# OpenMoteSTM-Border_MCU.net
KiCad netlist of a schematic drawn in Altium Designer
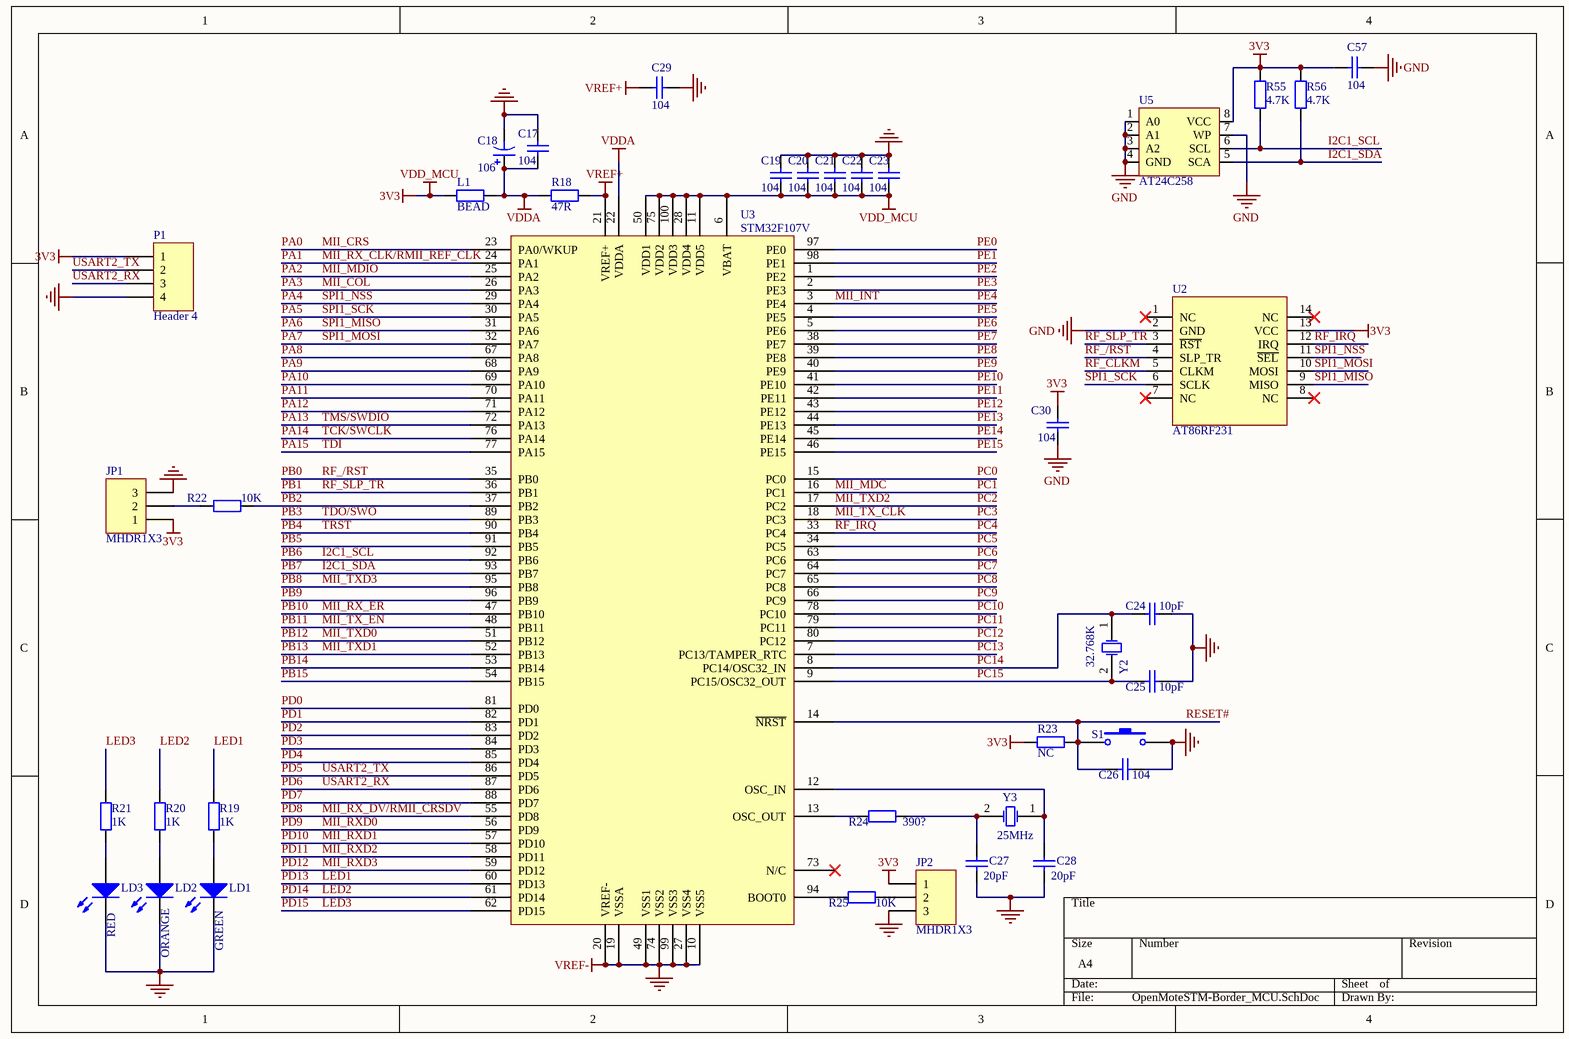
[diagram p0: OpenMoteSTM-Border_MCU.SchDoc]

(export (version "E")
  (design (tool "Eeschema 10.0.6"))
  (components
    (comp (ref "C17")
      (value "104")
      (footprint "0603")
      (description "Capacitor")
      (fields (field (name "Comment") "Cap") (field (name "PUBLISHER") "Altium Limited"))
      (libsource (lib "Miscellaneous Devices") (part "Cap"))
    )
    (comp (ref "C18")
      (value "106")
      (footprint "1210")
      (description "Polarized Capacitor (Radial)")
      (fields (field (name "Comment") "Cap Pol1") (field (name "PUBLISHER") "Altium Limited"))
      (libsource (lib "Miscellaneous Devices") (part "Cap Pol1"))
    )
    (comp (ref "C19")
      (value "104")
      (footprint "0603")
      (description "Capacitor")
      (fields (field (name "Comment") "Cap") (field (name "PUBLISHER") "Altium Limited"))
      (libsource (lib "Miscellaneous Devices") (part "Cap"))
    )
    (comp (ref "C20")
      (value "104")
      (footprint "0603")
      (description "Capacitor")
      (fields (field (name "Comment") "Cap") (field (name "PUBLISHER") "Altium Limited"))
      (libsource (lib "Miscellaneous Devices") (part "Cap"))
    )
    (comp (ref "C21")
      (value "104")
      (footprint "0603")
      (description "Capacitor")
      (fields (field (name "Comment") "Cap") (field (name "PUBLISHER") "Altium Limited"))
      (libsource (lib "Miscellaneous Devices") (part "Cap"))
    )
    (comp (ref "C22")
      (value "104")
      (footprint "0603")
      (description "Capacitor")
      (fields (field (name "Comment") "Cap") (field (name "PUBLISHER") "Altium Limited"))
      (libsource (lib "Miscellaneous Devices") (part "Cap"))
    )
    (comp (ref "C23")
      (value "104")
      (footprint "0603")
      (description "Capacitor")
      (fields (field (name "Comment") "Cap") (field (name "PUBLISHER") "Altium Limited"))
      (libsource (lib "Miscellaneous Devices") (part "Cap"))
    )
    (comp (ref "C24")
      (value "10pF")
      (footprint "0603")
      (description "Capacitor")
      (fields (field (name "Comment") "Cap") (field (name "PUBLISHER") "Altium Limited"))
      (libsource (lib "Miscellaneous Devices") (part "Cap"))
    )
    (comp (ref "C25")
      (value "10pF")
      (footprint "0603")
      (description "Capacitor")
      (fields (field (name "Comment") "Cap") (field (name "PUBLISHER") "Altium Limited"))
      (libsource (lib "Miscellaneous Devices") (part "Cap"))
    )
    (comp (ref "C26")
      (value "104")
      (footprint "0603")
      (description "Capacitor")
      (fields (field (name "Comment") "Cap") (field (name "PUBLISHER") "Altium Limited"))
      (libsource (lib "Miscellaneous Devices") (part "Cap"))
    )
    (comp (ref "C27")
      (value "20pF")
      (footprint "0603")
      (description "Capacitor")
      (fields (field (name "Comment") "Cap") (field (name "PUBLISHER") "Altium Limited"))
      (libsource (lib "Miscellaneous Devices") (part "Cap"))
    )
    (comp (ref "C28")
      (value "20pF")
      (footprint "0603")
      (description "Capacitor")
      (fields (field (name "Comment") "Cap") (field (name "PUBLISHER") "Altium Limited"))
      (libsource (lib "Miscellaneous Devices") (part "Cap"))
    )
    (comp (ref "C29")
      (value "104")
      (footprint "0603")
      (description "Capacitor")
      (fields (field (name "Comment") "Cap") (field (name "PUBLISHER") "Altium Limited"))
      (libsource (lib "Miscellaneous Devices") (part "Cap"))
    )
    (comp (ref "C30")
      (value "104")
      (footprint "0603")
      (description "Capacitor")
      (fields (field (name "Comment") "Cap") (field (name "PUBLISHER") "Altium Limited"))
      (libsource (lib "Miscellaneous Devices") (part "Cap"))
    )
    (comp (ref "C57")
      (value "104")
      (footprint "0603")
      (description "Capacitor")
      (fields (field (name "Comment") "Cap") (field (name "PUBLISHER") "Altium Limited"))
      (libsource (lib "Miscellaneous Devices") (part "Cap"))
    )
    (comp (ref "JP1")
      (value "MHDR1X3")
      (footprint "MHDR1X3")
      (description "Header, 3-Pin")
      (fields (field (name "PUBLISHER") "Altium Limited"))
      (libsource (lib "Miscellaneous Connectors") (part "MHDR1X3"))
    )
    (comp (ref "JP2")
      (value "MHDR1X3")
      (footprint "MHDR1X3")
      (description "Header, 3-Pin")
      (fields (field (name "PUBLISHER") "Altium Limited"))
      (libsource (lib "") (part "MHDR1X3_1"))
    )
    (comp (ref "L1")
      (value "BEAD")
      (footprint "0603")
      (description "Resistor")
      (fields (field (name "Comment") "Res2") (field (name "PUBLISHER") "Altium Limited"))
      (libsource (lib "Miscellaneous Devices") (part "Res2"))
    )
    (comp (ref "LD1")
      (value "GREEN")
      (footprint "0603")
      (description "Typical RED, GREEN, YELLOW, AMBER GaAs LED")
      (fields (field (name "PUBLISHER") "Altium Limited"))
      (libsource (lib "Miscellaneous Devices") (part "LED2"))
    )
    (comp (ref "LD2")
      (value "ORANGE")
      (footprint "0603")
      (description "Typical RED, GREEN, YELLOW, AMBER GaAs LED")
      (fields (field (name "PUBLISHER") "Altium Limited"))
      (libsource (lib "Miscellaneous Devices") (part "LED2"))
    )
    (comp (ref "LD3")
      (value "RED")
      (footprint "0603")
      (description "Typical RED, GREEN, YELLOW, AMBER GaAs LED")
      (fields (field (name "PUBLISHER") "Altium Limited"))
      (libsource (lib "Miscellaneous Devices") (part "LED2"))
    )
    (comp (ref "P1")
      (value "Header 4")
      (footprint "HDR1X4")
      (description "Header, 4-Pin")
      (fields (field (name "PUBLISHER") "Altium Limited"))
      (libsource (lib "Miscellaneous Connectors") (part "Header 4"))
    )
    (comp (ref "R18")
      (value "47R")
      (footprint "0603")
      (description "Resistor")
      (fields (field (name "Comment") "Res2") (field (name "PUBLISHER") "Altium Limited"))
      (libsource (lib "Miscellaneous Devices") (part "Res2"))
    )
    (comp (ref "R19")
      (value "1K")
      (footprint "0603")
      (description "Resistor")
      (fields (field (name "Comment") "Res2") (field (name "PUBLISHER") "Altium Limited"))
      (libsource (lib "") (part "Res2_2"))
    )
    (comp (ref "R20")
      (value "1K")
      (footprint "0603")
      (description "Resistor")
      (fields (field (name "Comment") "Res2") (field (name "PUBLISHER") "Altium Limited"))
      (libsource (lib "") (part "Res2_2"))
    )
    (comp (ref "R21")
      (value "1K")
      (footprint "0603")
      (description "Resistor")
      (fields (field (name "Comment") "Res2") (field (name "PUBLISHER") "Altium Limited"))
      (libsource (lib "") (part "Res2_2"))
    )
    (comp (ref "R22")
      (value "10K")
      (footprint "0603")
      (description "Resistor")
      (fields (field (name "Comment") "Res2") (field (name "PUBLISHER") "Altium Limited"))
      (libsource (lib "") (part "Res2_1"))
    )
    (comp (ref "R23")
      (value "NC")
      (footprint "0603")
      (description "Resistor")
      (fields (field (name "Comment") "Res2") (field (name "PUBLISHER") "Altium Limited"))
      (libsource (lib "") (part "Res2_1"))
    )
    (comp (ref "R24")
      (value "390?")
      (footprint "0603")
      (description "Resistor")
      (fields (field (name "Comment") "Res2") (field (name "PUBLISHER") "Altium Limited"))
      (libsource (lib "Miscellaneous Devices") (part "Res2"))
    )
    (comp (ref "R25")
      (value "10K")
      (footprint "0603")
      (description "Resistor")
      (fields (field (name "Comment") "Res2") (field (name "PUBLISHER") "Altium Limited"))
      (libsource (lib "") (part "Res2_1"))
    )
    (comp (ref "R55")
      (value "4.7K")
      (footprint "0603")
      (description "Resistor")
      (fields (field (name "Comment") "Res2") (field (name "PUBLISHER") "Altium Limited"))
      (libsource (lib "") (part "Res2_2"))
    )
    (comp (ref "R56")
      (value "4.7K")
      (footprint "0603")
      (description "Resistor")
      (fields (field (name "Comment") "Res2") (field (name "PUBLISHER") "Altium Limited"))
      (libsource (lib "") (part "Res2_2"))
    )
    (comp (ref "S1")
      (value "SW-PB")
      (footprint "KEY-SMD")
      (description "Switch")
      (fields (field (name "PUBLISHER") "Altium Limited"))
      (libsource (lib "Miscellaneous Devices") (part "SW-PB"))
    )
    (comp (ref "U2")
      (value "AT86RF231")
      (footprint "AT86RF231")
      (libsource (lib "OpenMoteSTM-Border") (part "AT86RF231"))
    )
    (comp (ref "U3")
      (value "STM32F107V")
      (footprint "STM32F107")
      (libsource (lib "OpenMoteSTM-Border") (part "STM32F107V"))
    )
    (comp (ref "U5")
      (value "AT24C258")
      (footprint "AT24C256C")
      (libsource (lib "OpenMoteSTM-Border") (part "AT24C258"))
    )
    (comp (ref "Y2")
      (value "32.768K")
      (footprint "32.768K")
      (description "Crystal Oscillator")
      (fields (field (name "PUBLISHER") "Altium Limited"))
      (libsource (lib "Miscellaneous Devices") (part "XTAL"))
    )
    (comp (ref "Y3")
      (value "25MHz")
      (footprint "XTAL")
      (description "Crystal Oscillator")
      (fields (field (name "PUBLISHER") "Altium Limited"))
      (libsource (lib "Miscellaneous Devices") (part "XTAL"))
    )
  )
  (nets
    (net (code "1") (name "/I2C1_SCL") (class "Default")
      (node (ref "R55") (pin "2") (pinfunction "2_2") (pintype "passive"))
      (node (ref "U3") (pin "92") (pinfunction "PB6_92") (pintype "passive"))
      (node (ref "U5") (pin "6") (pinfunction "SCL_6") (pintype "passive"))
    )
    (net (code "2") (name "/I2C1_SDA") (class "Default")
      (node (ref "R56") (pin "2") (pinfunction "2_2") (pintype "passive"))
      (node (ref "U3") (pin "93") (pinfunction "PB7_93") (pintype "passive"))
      (node (ref "U5") (pin "5") (pinfunction "SCA_5") (pintype "passive"))
    )
    (net (code "3") (name "/LED1") (class "Default")
      (node (ref "R19") (pin "1") (pinfunction "1_1") (pintype "passive"))
      (node (ref "U3") (pin "60") (pinfunction "PD13_60") (pintype "passive"))
    )
    (net (code "4") (name "/LED2") (class "Default")
      (node (ref "R20") (pin "1") (pinfunction "1_1") (pintype "passive"))
      (node (ref "U3") (pin "61") (pinfunction "PD14_61") (pintype "passive"))
    )
    (net (code "5") (name "/LED3") (class "Default")
      (node (ref "R21") (pin "1") (pinfunction "1_1") (pintype "passive"))
      (node (ref "U3") (pin "62") (pinfunction "PD15_62") (pintype "passive"))
    )
    (net (code "6") (name "/MII_COL") (class "Default")
      (node (ref "U3") (pin "26") (pinfunction "PA3_26") (pintype "passive"))
    )
    (net (code "7") (name "/MII_CRS") (class "Default")
      (node (ref "U3") (pin "23") (pinfunction "PA0/WKUP_23") (pintype "passive"))
    )
    (net (code "8") (name "/MII_INT") (class "Default")
      (node (ref "U3") (pin "3") (pinfunction "PE4_3") (pintype "passive"))
    )
    (net (code "9") (name "/MII_MDC") (class "Default")
      (node (ref "U3") (pin "16") (pinfunction "PC1_16") (pintype "passive"))
    )
    (net (code "10") (name "/MII_MDIO") (class "Default")
      (node (ref "U3") (pin "25") (pinfunction "PA2_25") (pintype "passive"))
    )
    (net (code "11") (name "/MII_RXD0") (class "Default")
      (node (ref "U3") (pin "56") (pinfunction "PD9_56") (pintype "passive"))
    )
    (net (code "12") (name "/MII_RXD1") (class "Default")
      (node (ref "U3") (pin "57") (pinfunction "PD10_57") (pintype "passive"))
    )
    (net (code "13") (name "/MII_RXD2") (class "Default")
      (node (ref "U3") (pin "58") (pinfunction "PD11_58") (pintype "passive"))
    )
    (net (code "14") (name "/MII_RXD3") (class "Default")
      (node (ref "U3") (pin "59") (pinfunction "PD12_59") (pintype "passive"))
    )
    (net (code "15") (name "/MII_RX_CLK{slash}RMII_REF_CLK") (class "Default")
      (node (ref "U3") (pin "24") (pinfunction "PA1_24") (pintype "passive"))
    )
    (net (code "16") (name "/MII_RX_DV{slash}RMII_CRSDV") (class "Default")
      (node (ref "U3") (pin "55") (pinfunction "PD8_55") (pintype "passive"))
    )
    (net (code "17") (name "/MII_RX_ER") (class "Default")
      (node (ref "U3") (pin "47") (pinfunction "PB10_47") (pintype "passive"))
    )
    (net (code "18") (name "/MII_TXD0") (class "Default")
      (node (ref "U3") (pin "51") (pinfunction "PB12_51") (pintype "passive"))
    )
    (net (code "19") (name "/MII_TXD1") (class "Default")
      (node (ref "U3") (pin "52") (pinfunction "PB13_52") (pintype "passive"))
    )
    (net (code "20") (name "/MII_TXD2") (class "Default")
      (node (ref "U3") (pin "17") (pinfunction "PC2_17") (pintype "passive"))
    )
    (net (code "21") (name "/MII_TXD3") (class "Default")
      (node (ref "U3") (pin "95") (pinfunction "PB8_95") (pintype "passive"))
    )
    (net (code "22") (name "/MII_TX_CLK") (class "Default")
      (node (ref "U3") (pin "18") (pinfunction "PC3_18") (pintype "passive"))
    )
    (net (code "23") (name "/MII_TX_EN") (class "Default")
      (node (ref "U3") (pin "48") (pinfunction "PB11_48") (pintype "passive"))
    )
    (net (code "24") (name "/PA4") (class "Default")
      (node (ref "U2") (pin "11") (pinfunction "~{SEL}_11") (pintype "passive"))
      (node (ref "U3") (pin "29") (pinfunction "PA4_29") (pintype "passive"))
    )
    (net (code "25") (name "/PA5") (class "Default")
      (node (ref "U2") (pin "6") (pinfunction "SCLK_6") (pintype "passive"))
      (node (ref "U3") (pin "30") (pinfunction "PA5_30") (pintype "passive"))
    )
    (net (code "26") (name "/PA6") (class "Default")
      (node (ref "U2") (pin "9") (pinfunction "MISO_9") (pintype "passive"))
      (node (ref "U3") (pin "31") (pinfunction "PA6_31") (pintype "passive"))
    )
    (net (code "27") (name "/PA7") (class "Default")
      (node (ref "U2") (pin "10") (pinfunction "MOSI_10") (pintype "passive"))
      (node (ref "U3") (pin "32") (pinfunction "PA7_32") (pintype "passive"))
    )
    (net (code "28") (name "/PA8") (class "Default")
      (node (ref "U3") (pin "67") (pinfunction "PA8_67") (pintype "passive"))
    )
    (net (code "29") (name "/PA9") (class "Default")
      (node (ref "U3") (pin "68") (pinfunction "PA9_68") (pintype "passive"))
    )
    (net (code "30") (name "/PA10") (class "Default")
      (node (ref "U3") (pin "69") (pinfunction "PA10_69") (pintype "passive"))
    )
    (net (code "31") (name "/PA11") (class "Default")
      (node (ref "U3") (pin "70") (pinfunction "PA11_70") (pintype "passive"))
    )
    (net (code "32") (name "/PA12") (class "Default")
      (node (ref "U3") (pin "71") (pinfunction "PA12_71") (pintype "passive"))
    )
    (net (code "33") (name "/PA13") (class "Default")
      (node (ref "U3") (pin "72") (pinfunction "PA13_72") (pintype "passive"))
    )
    (net (code "34") (name "/PA14") (class "Default")
      (node (ref "U3") (pin "76") (pinfunction "PA14_76") (pintype "passive"))
    )
    (net (code "35") (name "/PA15") (class "Default")
      (node (ref "U3") (pin "77") (pinfunction "PA15_77") (pintype "passive"))
    )
    (net (code "36") (name "/PB0") (class "Default")
      (node (ref "U2") (pin "4") (pinfunction "SLP_TR_4") (pintype "passive"))
      (node (ref "U3") (pin "35") (pinfunction "PB0_35") (pintype "passive"))
    )
    (net (code "37") (name "/PB1") (class "Default")
      (node (ref "U2") (pin "3") (pinfunction "~{RST}_3") (pintype "passive"))
      (node (ref "U3") (pin "36") (pinfunction "PB1_36") (pintype "passive"))
    )
    (net (code "38") (name "/PB2") (class "Default")
      (node (ref "R22") (pin "1") (pinfunction "1_1") (pintype "passive"))
      (node (ref "U3") (pin "37") (pinfunction "PB2_37") (pintype "passive"))
    )
    (net (code "39") (name "/PB3") (class "Default")
      (node (ref "U3") (pin "89") (pinfunction "PB3_89") (pintype "passive"))
    )
    (net (code "40") (name "/PB4") (class "Default")
      (node (ref "U3") (pin "90") (pinfunction "PB4_90") (pintype "passive"))
    )
    (net (code "41") (name "/PB5") (class "Default")
      (node (ref "U3") (pin "91") (pinfunction "PB5_91") (pintype "passive"))
    )
    (net (code "42") (name "/PB9") (class "Default")
      (node (ref "U3") (pin "96") (pinfunction "PB9_96") (pintype "passive"))
    )
    (net (code "43") (name "/PB14") (class "Default")
      (node (ref "U3") (pin "53") (pinfunction "PB14_53") (pintype "passive"))
    )
    (net (code "44") (name "/PB15") (class "Default")
      (node (ref "U3") (pin "54") (pinfunction "PB15_54") (pintype "passive"))
    )
    (net (code "45") (name "/PC0") (class "Default")
      (node (ref "U3") (pin "15") (pinfunction "PC0_15") (pintype "passive"))
    )
    (net (code "46") (name "/PC4") (class "Default")
      (node (ref "U2") (pin "12") (pinfunction "IRQ_12") (pintype "passive"))
      (node (ref "U3") (pin "33") (pinfunction "PC4_33") (pintype "passive"))
    )
    (net (code "47") (name "/PC5") (class "Default")
      (node (ref "U3") (pin "34") (pinfunction "PC5_34") (pintype "passive"))
    )
    (net (code "48") (name "/PC6") (class "Default")
      (node (ref "U3") (pin "63") (pinfunction "PC6_63") (pintype "passive"))
    )
    (net (code "49") (name "/PC7") (class "Default")
      (node (ref "U3") (pin "64") (pinfunction "PC7_64") (pintype "passive"))
    )
    (net (code "50") (name "/PC8") (class "Default")
      (node (ref "U3") (pin "65") (pinfunction "PC8_65") (pintype "passive"))
    )
    (net (code "51") (name "/PC9") (class "Default")
      (node (ref "U3") (pin "66") (pinfunction "PC9_66") (pintype "passive"))
    )
    (net (code "52") (name "/PC10") (class "Default")
      (node (ref "U3") (pin "78") (pinfunction "PC10_78") (pintype "passive"))
    )
    (net (code "53") (name "/PC11") (class "Default")
      (node (ref "U3") (pin "79") (pinfunction "PC11_79") (pintype "passive"))
    )
    (net (code "54") (name "/PC12") (class "Default")
      (node (ref "U3") (pin "80") (pinfunction "PC12_80") (pintype "passive"))
    )
    (net (code "55") (name "/PC13") (class "Default")
      (node (ref "U3") (pin "7") (pinfunction "PC13/TAMPER_RTC_7") (pintype "passive"))
    )
    (net (code "56") (name "/PC14") (class "Default")
      (node (ref "C24") (pin "2") (pinfunction "2_2") (pintype "passive"))
      (node (ref "U3") (pin "8") (pinfunction "PC14/OSC32_IN_8") (pintype "passive"))
      (node (ref "Y2") (pin "1") (pinfunction "OSC1_1") (pintype "passive"))
    )
    (net (code "57") (name "/PC15") (class "Default")
      (node (ref "C25") (pin "1") (pinfunction "1_1") (pintype "passive"))
      (node (ref "U3") (pin "9") (pinfunction "PC15/OSC32_OUT_9") (pintype "passive"))
      (node (ref "Y2") (pin "2") (pinfunction "OSC2_2") (pintype "passive"))
    )
    (net (code "58") (name "/PD0") (class "Default")
      (node (ref "U3") (pin "81") (pinfunction "PD0_81") (pintype "passive"))
    )
    (net (code "59") (name "/PD1") (class "Default")
      (node (ref "U3") (pin "82") (pinfunction "PD1_82") (pintype "passive"))
    )
    (net (code "60") (name "/PD2") (class "Default")
      (node (ref "U3") (pin "83") (pinfunction "PD2_83") (pintype "passive"))
    )
    (net (code "61") (name "/PD3") (class "Default")
      (node (ref "U3") (pin "84") (pinfunction "PD3_84") (pintype "passive"))
    )
    (net (code "62") (name "/PD4") (class "Default")
      (node (ref "U3") (pin "85") (pinfunction "PD4_85") (pintype "passive"))
    )
    (net (code "63") (name "/PD5") (class "Default")
      (node (ref "P1") (pin "2") (pinfunction "2_2") (pintype "passive"))
      (node (ref "U3") (pin "86") (pinfunction "PD5_86") (pintype "passive"))
    )
    (net (code "64") (name "/PD6") (class "Default")
      (node (ref "P1") (pin "3") (pinfunction "3_3") (pintype "passive"))
      (node (ref "U3") (pin "87") (pinfunction "PD6_87") (pintype "passive"))
    )
    (net (code "65") (name "/PD7") (class "Default")
      (node (ref "U3") (pin "88") (pinfunction "PD7_88") (pintype "passive"))
    )
    (net (code "66") (name "/PE0") (class "Default")
      (node (ref "U3") (pin "97") (pinfunction "PE0_97") (pintype "passive"))
    )
    (net (code "67") (name "/PE1") (class "Default")
      (node (ref "U3") (pin "98") (pinfunction "PE1_98") (pintype "passive"))
    )
    (net (code "68") (name "/PE2") (class "Default")
      (node (ref "U3") (pin "1") (pinfunction "PE2_1") (pintype "passive"))
    )
    (net (code "69") (name "/PE3") (class "Default")
      (node (ref "U3") (pin "2") (pinfunction "PE3_2") (pintype "passive"))
    )
    (net (code "70") (name "/PE5") (class "Default")
      (node (ref "U3") (pin "4") (pinfunction "PE5_4") (pintype "passive"))
    )
    (net (code "71") (name "/PE6") (class "Default")
      (node (ref "U3") (pin "5") (pinfunction "PE6_5") (pintype "passive"))
    )
    (net (code "72") (name "/PE7") (class "Default")
      (node (ref "U3") (pin "38") (pinfunction "PE7_38") (pintype "passive"))
    )
    (net (code "73") (name "/PE8") (class "Default")
      (node (ref "U3") (pin "39") (pinfunction "PE8_39") (pintype "passive"))
    )
    (net (code "74") (name "/PE9") (class "Default")
      (node (ref "U3") (pin "40") (pinfunction "PE9_40") (pintype "passive"))
    )
    (net (code "75") (name "/PE10") (class "Default")
      (node (ref "U3") (pin "41") (pinfunction "PE10_41") (pintype "passive"))
    )
    (net (code "76") (name "/PE11") (class "Default")
      (node (ref "U3") (pin "42") (pinfunction "PE11_42") (pintype "passive"))
    )
    (net (code "77") (name "/PE12") (class "Default")
      (node (ref "U3") (pin "43") (pinfunction "PE12_43") (pintype "passive"))
    )
    (net (code "78") (name "/PE13") (class "Default")
      (node (ref "U3") (pin "44") (pinfunction "PE13_44") (pintype "passive"))
    )
    (net (code "79") (name "/PE14") (class "Default")
      (node (ref "U3") (pin "45") (pinfunction "PE14_45") (pintype "passive"))
    )
    (net (code "80") (name "/PE15") (class "Default")
      (node (ref "U3") (pin "46") (pinfunction "PE15_46") (pintype "passive"))
    )
    (net (code "81") (name "/RESET#") (class "Default")
      (node (ref "C26") (pin "2") (pinfunction "2_2") (pintype "passive"))
      (node (ref "R23") (pin "1") (pinfunction "1_1") (pintype "passive"))
      (node (ref "S1") (pin "1") (pinfunction "1_1") (pintype "passive"))
      (node (ref "U3") (pin "14") (pinfunction "~{NRST}_14") (pintype "passive"))
    )
    (net (code "82") (name "/RF_CLKM") (class "Default")
      (node (ref "U2") (pin "5") (pinfunction "CLKM_5") (pintype "passive"))
    )
    (net (code "83") (name "3V3") (class "Default")
      (node (ref "C19") (pin "1") (pinfunction "1_1") (pintype "passive"))
      (node (ref "C20") (pin "1") (pinfunction "1_1") (pintype "passive"))
      (node (ref "C21") (pin "1") (pinfunction "1_1") (pintype "passive"))
      (node (ref "C22") (pin "1") (pinfunction "1_1") (pintype "passive"))
      (node (ref "C23") (pin "1") (pinfunction "1_1") (pintype "passive"))
      (node (ref "C30") (pin "2") (pinfunction "2_2") (pintype "passive"))
      (node (ref "C57") (pin "2") (pinfunction "2_2") (pintype "passive"))
      (node (ref "JP1") (pin "1") (pinfunction "1_1") (pintype "passive"))
      (node (ref "JP2") (pin "1") (pinfunction "1_1") (pintype "passive"))
      (node (ref "L1") (pin "1") (pinfunction "1_1") (pintype "passive"))
      (node (ref "P1") (pin "1") (pinfunction "1_1") (pintype "passive"))
      (node (ref "R23") (pin "2") (pinfunction "2_2") (pintype "passive"))
      (node (ref "R55") (pin "1") (pinfunction "1_1") (pintype "passive"))
      (node (ref "R56") (pin "1") (pinfunction "1_1") (pintype "passive"))
      (node (ref "U2") (pin "13") (pinfunction "VCC_13") (pintype "passive"))
      (node (ref "U3") (pin "100") (pinfunction "VDD3_100") (pintype "passive"))
      (node (ref "U3") (pin "11") (pinfunction "VDD5_11") (pintype "passive"))
      (node (ref "U3") (pin "28") (pinfunction "VDD4_28") (pintype "passive"))
      (node (ref "U3") (pin "50") (pinfunction "VDD1_50") (pintype "passive"))
      (node (ref "U3") (pin "6") (pinfunction "VBAT_6") (pintype "passive"))
      (node (ref "U3") (pin "75") (pinfunction "VDD2_75") (pintype "passive"))
      (node (ref "U5") (pin "8") (pinfunction "VCC_8") (pintype "passive"))
    )
    (net (code "84") (name "GND") (class "Default")
      (node (ref "C17") (pin "2") (pinfunction "2_2") (pintype "passive"))
      (node (ref "C18") (pin "2") (pinfunction "2_2") (pintype "passive"))
      (node (ref "C19") (pin "2") (pinfunction "2_2") (pintype "passive"))
      (node (ref "C20") (pin "2") (pinfunction "2_2") (pintype "passive"))
      (node (ref "C21") (pin "2") (pinfunction "2_2") (pintype "passive"))
      (node (ref "C22") (pin "2") (pinfunction "2_2") (pintype "passive"))
      (node (ref "C23") (pin "2") (pinfunction "2_2") (pintype "passive"))
      (node (ref "C24") (pin "1") (pinfunction "1_1") (pintype "passive"))
      (node (ref "C25") (pin "2") (pinfunction "2_2") (pintype "passive"))
      (node (ref "C26") (pin "1") (pinfunction "1_1") (pintype "passive"))
      (node (ref "C27") (pin "2") (pinfunction "2_2") (pintype "passive"))
      (node (ref "C28") (pin "2") (pinfunction "2_2") (pintype "passive"))
      (node (ref "C29") (pin "2") (pinfunction "2_2") (pintype "passive"))
      (node (ref "C30") (pin "1") (pinfunction "1_1") (pintype "passive"))
      (node (ref "C57") (pin "1") (pinfunction "1_1") (pintype "passive"))
      (node (ref "JP1") (pin "3") (pinfunction "3_3") (pintype "passive"))
      (node (ref "JP2") (pin "3") (pinfunction "3_3") (pintype "passive"))
      (node (ref "LD1") (pin "2") (pinfunction "K_2") (pintype "passive"))
      (node (ref "LD2") (pin "2") (pinfunction "K_2") (pintype "passive"))
      (node (ref "LD3") (pin "2") (pinfunction "K_2") (pintype "passive"))
      (node (ref "P1") (pin "4") (pinfunction "4_4") (pintype "passive"))
      (node (ref "S1") (pin "2") (pinfunction "2_2") (pintype "passive"))
      (node (ref "U2") (pin "2") (pinfunction "GND_2") (pintype "passive"))
      (node (ref "U3") (pin "10") (pinfunction "VSS5_10") (pintype "passive"))
      (node (ref "U3") (pin "19") (pinfunction "VSSA_19") (pintype "passive"))
      (node (ref "U3") (pin "20") (pinfunction "VREF-_20") (pintype "passive"))
      (node (ref "U3") (pin "27") (pinfunction "VSS4_27") (pintype "passive"))
      (node (ref "U3") (pin "49") (pinfunction "VSS1_49") (pintype "passive"))
      (node (ref "U3") (pin "74") (pinfunction "VSS2_74") (pintype "passive"))
      (node (ref "U3") (pin "99") (pinfunction "VSS3_99") (pintype "passive"))
      (node (ref "U5") (pin "1") (pinfunction "A0_1") (pintype "passive"))
      (node (ref "U5") (pin "2") (pinfunction "A1_2") (pintype "passive"))
      (node (ref "U5") (pin "3") (pinfunction "A2_3") (pintype "passive"))
      (node (ref "U5") (pin "4") (pinfunction "GND_4") (pintype "passive"))
      (node (ref "U5") (pin "7") (pinfunction "WP_7") (pintype "passive"))
    )
    (net (code "85") (name "Net-(JP1-Pad2)") (class "Default")
      (node (ref "JP1") (pin "2") (pinfunction "2_2") (pintype "passive"))
      (node (ref "R22") (pin "2") (pinfunction "2_2") (pintype "passive"))
    )
    (net (code "86") (name "Net-(JP2-Pad2)") (class "Default")
      (node (ref "JP2") (pin "2") (pinfunction "2_2") (pintype "passive"))
      (node (ref "R25") (pin "1") (pinfunction "1_1") (pintype "passive"))
    )
    (net (code "87") (name "Net-(LD1-A)") (class "Default")
      (node (ref "LD1") (pin "1") (pinfunction "A_1") (pintype "passive"))
      (node (ref "R19") (pin "2") (pinfunction "2_2") (pintype "passive"))
    )
    (net (code "88") (name "Net-(LD2-A)") (class "Default")
      (node (ref "LD2") (pin "1") (pinfunction "A_1") (pintype "passive"))
      (node (ref "R20") (pin "2") (pinfunction "2_2") (pintype "passive"))
    )
    (net (code "89") (name "Net-(LD3-A)") (class "Default")
      (node (ref "LD3") (pin "1") (pinfunction "A_1") (pintype "passive"))
      (node (ref "R21") (pin "2") (pinfunction "2_2") (pintype "passive"))
    )
    (net (code "90") (name "Net-(U3-BOOT0)") (class "Default")
      (node (ref "R25") (pin "2") (pinfunction "2_2") (pintype "passive"))
      (node (ref "U3") (pin "94") (pinfunction "BOOT0_94") (pintype "passive"))
    )
    (net (code "91") (name "Net-(U3-OSC_IN)") (class "Default")
      (node (ref "C28") (pin "1") (pinfunction "1_1") (pintype "passive"))
      (node (ref "U3") (pin "12") (pinfunction "OSC_IN_12") (pintype "passive"))
      (node (ref "Y3") (pin "1") (pinfunction "OSC1_1") (pintype "passive"))
    )
    (net (code "92") (name "Net-(U3-OSC_OUT)") (class "Default")
      (node (ref "R24") (pin "1") (pinfunction "1_1") (pintype "passive"))
      (node (ref "U3") (pin "13") (pinfunction "OSC_OUT_13") (pintype "passive"))
    )
    (net (code "93") (name "Net-(Y3-OSC2)") (class "Default")
      (node (ref "C27") (pin "1") (pinfunction "1_1") (pintype "passive"))
      (node (ref "R24") (pin "2") (pinfunction "2_2") (pintype "passive"))
      (node (ref "Y3") (pin "2") (pinfunction "OSC2_2") (pintype "passive"))
    )
    (net (code "94") (name "VDDA") (class "Default")
      (node (ref "C17") (pin "1") (pinfunction "1_1") (pintype "passive"))
      (node (ref "C18") (pin "1") (pinfunction "1_1") (pintype "passive"))
      (node (ref "L1") (pin "2") (pinfunction "2_2") (pintype "passive"))
      (node (ref "R18") (pin "1") (pinfunction "1_1") (pintype "passive"))
      (node (ref "U3") (pin "22") (pinfunction "VDDA_22") (pintype "passive"))
    )
    (net (code "95") (name "VREF+") (class "Default")
      (node (ref "C29") (pin "1") (pinfunction "1_1") (pintype "passive"))
      (node (ref "R18") (pin "2") (pinfunction "2_2") (pintype "passive"))
      (node (ref "U3") (pin "21") (pinfunction "VREF+_21") (pintype "passive"))
    )
    (net (code "96") (name "unconnected-(U2-NC-Pad1)") (class "Default")
      (node (ref "U2") (pin "1") (pinfunction "NC_1") (pintype "passive+no_connect"))
    )
    (net (code "97") (name "unconnected-(U2-NC-Pad7)") (class "Default")
      (node (ref "U2") (pin "7") (pinfunction "NC_7") (pintype "passive+no_connect"))
    )
    (net (code "98") (name "unconnected-(U2-NC-Pad8)") (class "Default")
      (node (ref "U2") (pin "8") (pinfunction "NC_8") (pintype "passive+no_connect"))
    )
    (net (code "99") (name "unconnected-(U2-NC-Pad14)") (class "Default")
      (node (ref "U2") (pin "14") (pinfunction "NC_14") (pintype "passive+no_connect"))
    )
    (net (code "100") (name "unconnected-(U3-N{slash}C-Pad73)") (class "Default")
      (node (ref "U3") (pin "73") (pinfunction "N/C_73") (pintype "passive+no_connect"))
    )
  )
)
